# LilypadShield.net
KiCad netlist of a schematic drawn in EAGLE
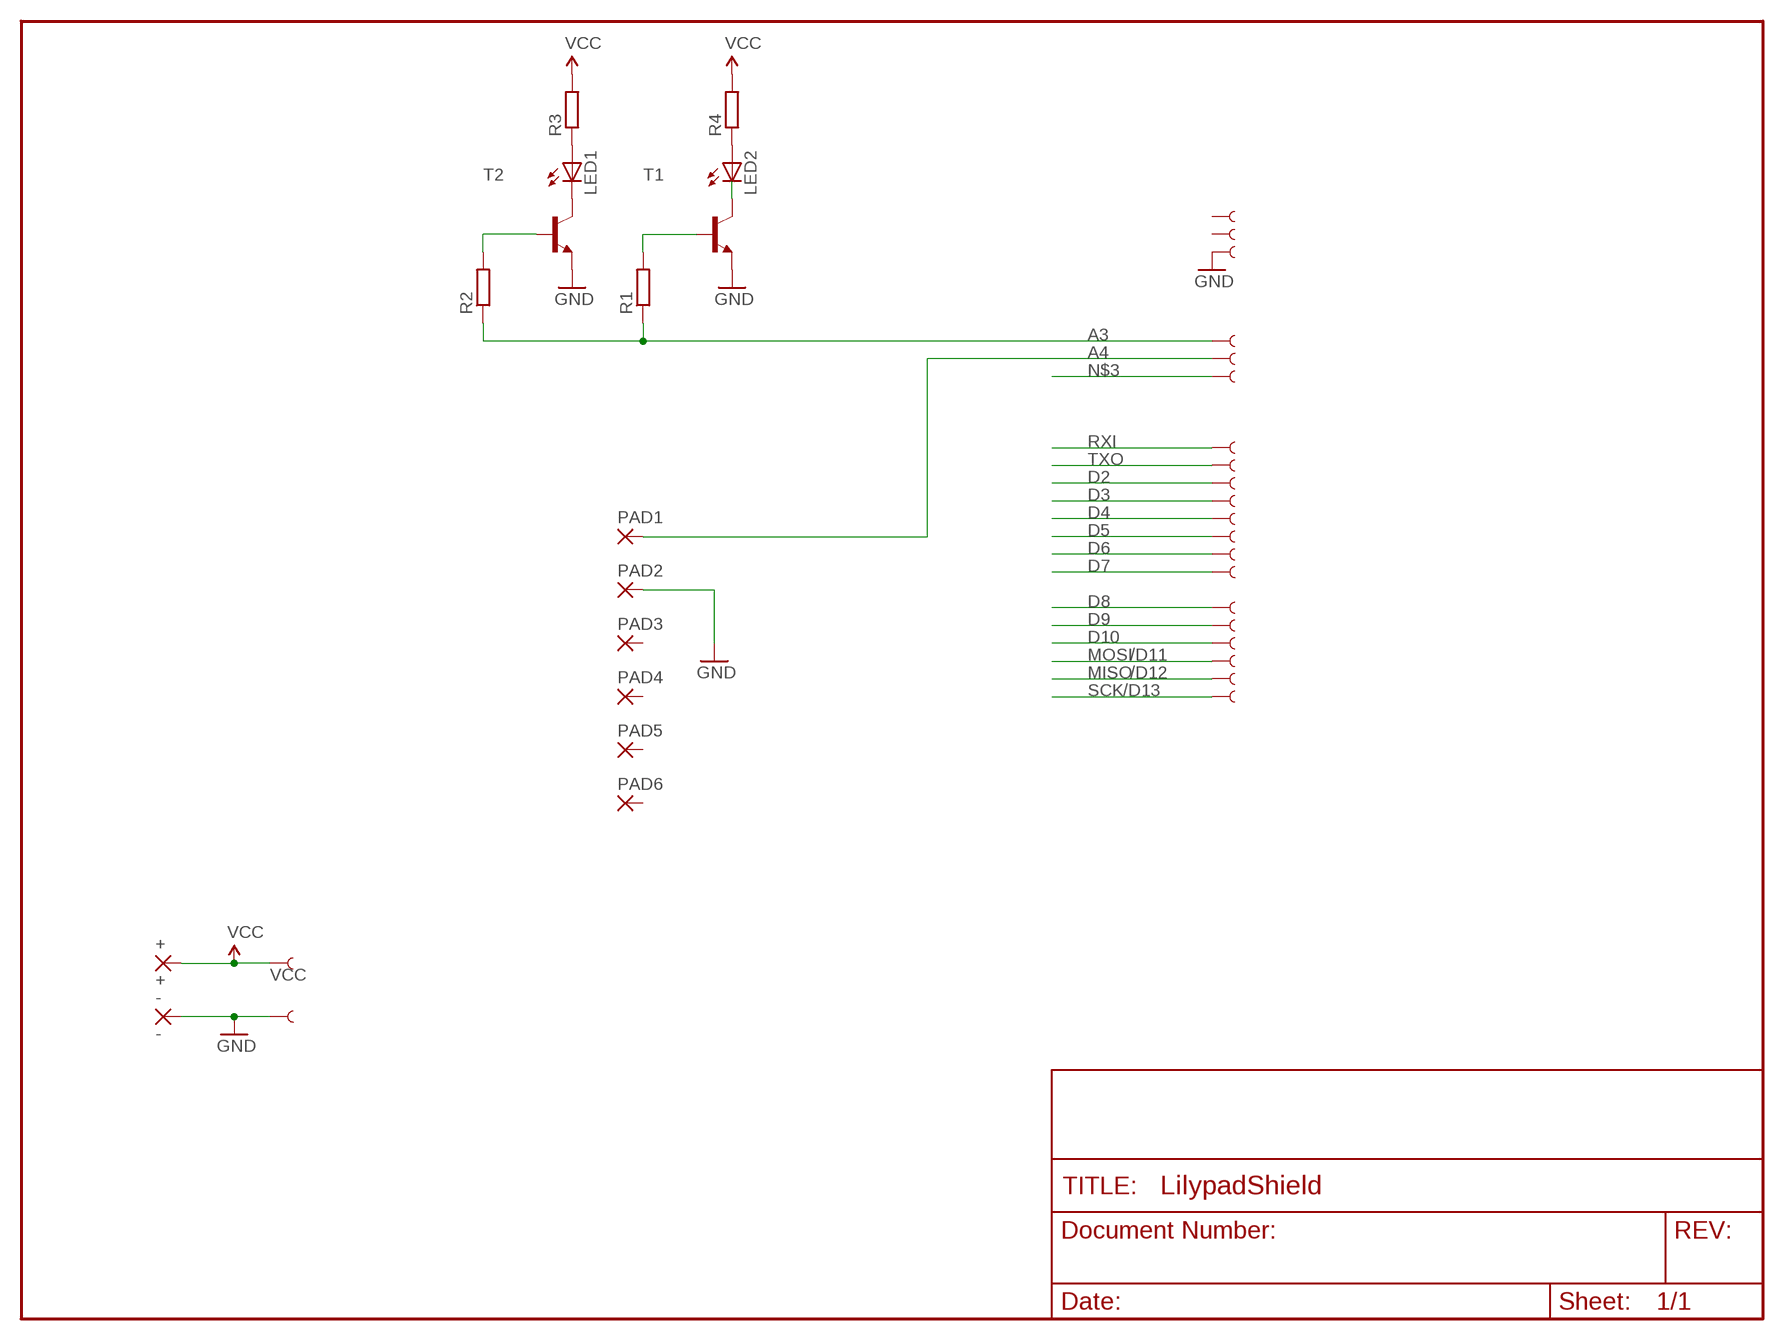
[diagram p0: schematic, sheet 1]

(export (version "E")
  (design (tool "Eeschema 10.0.6"))
  (components
    (comp (ref "+")
      (value "+")
      (footprint "eagle-import:1,6_0,8")
      (libsource (lib "eagle-import") (part "1,6/0,8"))
    )
    (comp (ref "-")
      (value "-")
      (footprint "eagle-import:1,6_0,8")
      (libsource (lib "eagle-import") (part "1,6/0,8"))
    )
    (comp (ref "GND")
      (value "SEWTAP1")
      (footprint "eagle-import:SEWTAP")
      (libsource (lib "eagle-import") (part "SEWTAP1"))
    )
    (comp (ref "LED1")
      (value "LED5MM")
      (footprint "eagle-import:LED5MM")
      (libsource (lib "eagle-import") (part "LED5MM"))
    )
    (comp (ref "LED2")
      (value "LED5MM")
      (footprint "eagle-import:LED5MM")
      (libsource (lib "eagle-import") (part "LED5MM"))
    )
    (comp (ref "PAD1")
      (value "1,6/0,8")
      (footprint "eagle-import:1,6_0,8")
      (libsource (lib "eagle-import") (part "1,6/0,8"))
    )
    (comp (ref "PAD2")
      (value "1,6/0,8")
      (footprint "eagle-import:1,6_0,8")
      (libsource (lib "eagle-import") (part "1,6/0,8"))
    )
    (comp (ref "PAD3")
      (value "1,6/0,8")
      (footprint "eagle-import:1,6_0,8")
      (libsource (lib "eagle-import") (part "1,6/0,8"))
    )
    (comp (ref "PAD4")
      (value "1,6/0,8")
      (footprint "eagle-import:1,6_0,8")
      (libsource (lib "eagle-import") (part "1,6/0,8"))
    )
    (comp (ref "PAD5")
      (value "1,6/0,8")
      (footprint "eagle-import:1,6_0,8")
      (libsource (lib "eagle-import") (part "1,6/0,8"))
    )
    (comp (ref "PAD6")
      (value "1,6/0,8")
      (footprint "eagle-import:1,6_0,8")
      (libsource (lib "eagle-import") (part "1,6/0,8"))
    )
    (comp (ref "R1")
      (value "R-EU_0204/5")
      (footprint "eagle-import:0204_5")
      (libsource (lib "eagle-import") (part "R-EU_0204/5"))
    )
    (comp (ref "R2")
      (value "R-EU_0204/5")
      (footprint "eagle-import:0204_5")
      (libsource (lib "eagle-import") (part "R-EU_0204/5"))
    )
    (comp (ref "R3")
      (value "R-EU_0204/5")
      (footprint "eagle-import:0204_5")
      (libsource (lib "eagle-import") (part "R-EU_0204/5"))
    )
    (comp (ref "R4")
      (value "R-EU_0204/5")
      (footprint "eagle-import:0204_5")
      (libsource (lib "eagle-import") (part "R-EU_0204/5"))
    )
    (comp (ref "T1")
      (value "2N3904")
      (footprint "eagle-import:TO92")
      (libsource (lib "eagle-import") (part "2N3904"))
    )
    (comp (ref "T2")
      (value "2N3904")
      (footprint "eagle-import:TO92")
      (libsource (lib "eagle-import") (part "2N3904"))
    )
    (comp (ref "U$4")
      (value "SEWTAP1")
      (footprint "eagle-import:SEWTAP")
      (libsource (lib "eagle-import") (part "SEWTAP1"))
    )
    (comp (ref "U$30")
      (value "SEWTAP1")
      (footprint "eagle-import:SEWTAP")
      (libsource (lib "eagle-import") (part "SEWTAP1"))
    )
    (comp (ref "U$31")
      (value "SEWTAP1")
      (footprint "eagle-import:SEWTAP")
      (libsource (lib "eagle-import") (part "SEWTAP1"))
    )
    (comp (ref "U$32")
      (value "SEWTAP1")
      (footprint "eagle-import:SEWTAP")
      (libsource (lib "eagle-import") (part "SEWTAP1"))
    )
    (comp (ref "U$33")
      (value "SEWTAP1")
      (footprint "eagle-import:SEWTAP")
      (libsource (lib "eagle-import") (part "SEWTAP1"))
    )
    (comp (ref "U$34")
      (value "SEWTAP1")
      (footprint "eagle-import:SEWTAP")
      (libsource (lib "eagle-import") (part "SEWTAP1"))
    )
    (comp (ref "U$35")
      (value "SEWTAP1")
      (footprint "eagle-import:SEWTAP")
      (libsource (lib "eagle-import") (part "SEWTAP1"))
    )
    (comp (ref "U$36")
      (value "SEWTAP1")
      (footprint "eagle-import:SEWTAP")
      (libsource (lib "eagle-import") (part "SEWTAP1"))
    )
    (comp (ref "U$37")
      (value "SEWTAP1")
      (footprint "eagle-import:SEWTAP")
      (libsource (lib "eagle-import") (part "SEWTAP1"))
    )
    (comp (ref "U$38")
      (value "SEWTAP1")
      (footprint "eagle-import:SEWTAP")
      (libsource (lib "eagle-import") (part "SEWTAP1"))
    )
    (comp (ref "U$39")
      (value "SEWTAP1")
      (footprint "eagle-import:SEWTAP")
      (libsource (lib "eagle-import") (part "SEWTAP1"))
    )
    (comp (ref "U$40")
      (value "SEWTAP1")
      (footprint "eagle-import:SEWTAP")
      (libsource (lib "eagle-import") (part "SEWTAP1"))
    )
    (comp (ref "U$41")
      (value "SEWTAP1")
      (footprint "eagle-import:SEWTAP")
      (libsource (lib "eagle-import") (part "SEWTAP1"))
    )
    (comp (ref "U$42")
      (value "SEWTAP1")
      (footprint "eagle-import:SEWTAP")
      (libsource (lib "eagle-import") (part "SEWTAP1"))
    )
    (comp (ref "U$43")
      (value "SEWTAP1")
      (footprint "eagle-import:SEWTAP")
      (libsource (lib "eagle-import") (part "SEWTAP1"))
    )
    (comp (ref "U$44")
      (value "SEWTAP1")
      (footprint "eagle-import:SEWTAP")
      (libsource (lib "eagle-import") (part "SEWTAP1"))
    )
    (comp (ref "U$45")
      (value "SEWTAP1")
      (footprint "eagle-import:SEWTAP")
      (libsource (lib "eagle-import") (part "SEWTAP1"))
    )
    (comp (ref "U$46")
      (value "SEWTAP1")
      (footprint "eagle-import:SEWTAP")
      (libsource (lib "eagle-import") (part "SEWTAP1"))
    )
    (comp (ref "U$47")
      (value "SEWTAP1")
      (footprint "eagle-import:SEWTAP")
      (libsource (lib "eagle-import") (part "SEWTAP1"))
    )
    (comp (ref "U$48")
      (value "SEWTAP1")
      (footprint "eagle-import:SEWTAP")
      (libsource (lib "eagle-import") (part "SEWTAP1"))
    )
    (comp (ref "U$51")
      (value "SEWTAP1")
      (footprint "eagle-import:SEWTAP")
      (libsource (lib "eagle-import") (part "SEWTAP1"))
    )
  )
  (nets
    (net (code "1") (name "/A3") (class "Default")
      (node (ref "R1") (pin "1") (pinfunction "1_1") (pintype "passive"))
      (node (ref "R2") (pin "1") (pinfunction "1_1") (pintype "passive"))
      (node (ref "U$32") (pin "1") (pinfunction "1_1") (pintype "bidirectional"))
    )
    (net (code "2") (name "/A4") (class "Default")
      (node (ref "PAD1") (pin "1") (pinfunction "P_1") (pintype "passive"))
      (node (ref "U$33") (pin "1") (pinfunction "1_1") (pintype "bidirectional"))
    )
    (net (code "3") (name "/D2") (class "Default")
      (node (ref "U$45") (pin "1") (pinfunction "1_1") (pintype "bidirectional"))
    )
    (net (code "4") (name "/D3") (class "Default")
      (node (ref "U$44") (pin "1") (pinfunction "1_1") (pintype "bidirectional"))
    )
    (net (code "5") (name "/D4") (class "Default")
      (node (ref "U$43") (pin "1") (pinfunction "1_1") (pintype "bidirectional"))
    )
    (net (code "6") (name "/D5") (class "Default")
      (node (ref "U$42") (pin "1") (pinfunction "1_1") (pintype "bidirectional"))
    )
    (net (code "7") (name "/D6") (class "Default")
      (node (ref "U$41") (pin "1") (pinfunction "1_1") (pintype "bidirectional"))
    )
    (net (code "8") (name "/D7") (class "Default")
      (node (ref "U$48") (pin "1") (pinfunction "1_1") (pintype "bidirectional"))
    )
    (net (code "9") (name "/D8") (class "Default")
      (node (ref "U$35") (pin "1") (pinfunction "1_1") (pintype "bidirectional"))
    )
    (net (code "10") (name "/D9") (class "Default")
      (node (ref "U$36") (pin "1") (pinfunction "1_1") (pintype "bidirectional"))
    )
    (net (code "11") (name "/D10") (class "Default")
      (node (ref "U$37") (pin "1") (pinfunction "1_1") (pintype "bidirectional"))
    )
    (net (code "12") (name "/MISO") (class "Default")
      (node (ref "U$39") (pin "1") (pinfunction "1_1") (pintype "bidirectional"))
    )
    (net (code "13") (name "/MOSI") (class "Default")
      (node (ref "U$38") (pin "1") (pinfunction "1_1") (pintype "bidirectional"))
    )
    (net (code "14") (name "/N$3") (class "Default")
      (node (ref "U$34") (pin "1") (pinfunction "1_1") (pintype "bidirectional"))
    )
    (net (code "15") (name "/RXI") (class "Default")
      (node (ref "U$47") (pin "1") (pinfunction "1_1") (pintype "bidirectional"))
    )
    (net (code "16") (name "/SCK") (class "Default")
      (node (ref "U$40") (pin "1") (pinfunction "1_1") (pintype "bidirectional"))
    )
    (net (code "17") (name "/TXO") (class "Default")
      (node (ref "U$46") (pin "1") (pinfunction "1_1") (pintype "bidirectional"))
    )
    (net (code "18") (name "GND") (class "Default")
      (node (ref "-") (pin "1") (pinfunction "P_1") (pintype "passive"))
      (node (ref "PAD2") (pin "1") (pinfunction "P_1") (pintype "passive"))
      (node (ref "T1") (pin "3") (pinfunction "E_3") (pintype "passive"))
      (node (ref "T2") (pin "3") (pinfunction "E_3") (pintype "passive"))
      (node (ref "U$30") (pin "1") (pinfunction "1_1") (pintype "bidirectional"))
      (node (ref "U$31") (pin "1") (pinfunction "1_1") (pintype "bidirectional"))
    )
    (net (code "19") (name "Net-(LED1-C)") (class "Default")
      (node (ref "LED1") (pin "K") (pinfunction "C_K") (pintype "passive"))
      (node (ref "T2") (pin "1") (pinfunction "C_1") (pintype "passive"))
    )
    (net (code "20") (name "Net-(LED1-PadA)") (class "Default")
      (node (ref "LED1") (pin "A") (pinfunction "A_A") (pintype "passive"))
      (node (ref "R3") (pin "1") (pinfunction "1_1") (pintype "passive"))
    )
    (net (code "21") (name "Net-(LED2-C)") (class "Default")
      (node (ref "LED2") (pin "K") (pinfunction "C_K") (pintype "passive"))
      (node (ref "T1") (pin "1") (pinfunction "C_1") (pintype "passive"))
    )
    (net (code "22") (name "Net-(LED2-PadA)") (class "Default")
      (node (ref "LED2") (pin "A") (pinfunction "A_A") (pintype "passive"))
      (node (ref "R4") (pin "1") (pinfunction "1_1") (pintype "passive"))
    )
    (net (code "23") (name "Net-(T1-B)") (class "Default")
      (node (ref "R1") (pin "2") (pinfunction "2_2") (pintype "passive"))
      (node (ref "T1") (pin "2") (pinfunction "B_2") (pintype "passive"))
    )
    (net (code "24") (name "Net-(T2-B)") (class "Default")
      (node (ref "R2") (pin "2") (pinfunction "2_2") (pintype "passive"))
      (node (ref "T2") (pin "2") (pinfunction "B_2") (pintype "passive"))
    )
    (net (code "25") (name "VCC") (class "Default")
      (node (ref "+") (pin "1") (pinfunction "P_1") (pintype "passive"))
      (node (ref "R3") (pin "2") (pinfunction "2_2") (pintype "passive"))
      (node (ref "R4") (pin "2") (pinfunction "2_2") (pintype "passive"))
      (node (ref "U$4") (pin "1") (pinfunction "1_1") (pintype "bidirectional"))
    )
    (net (code "26") (name "unconnected-(GND-Pad1)") (class "Default")
      (node (ref "GND") (pin "1") (pinfunction "1_1") (pintype "bidirectional"))
    )
    (net (code "27") (name "unconnected-(PAD3-P-Pad1)") (class "Default")
      (node (ref "PAD3") (pin "1") (pinfunction "P_1") (pintype "passive"))
    )
    (net (code "28") (name "unconnected-(PAD4-P-Pad1)") (class "Default")
      (node (ref "PAD4") (pin "1") (pinfunction "P_1") (pintype "passive"))
    )
    (net (code "29") (name "unconnected-(PAD5-P-Pad1)") (class "Default")
      (node (ref "PAD5") (pin "1") (pinfunction "P_1") (pintype "passive"))
    )
    (net (code "30") (name "unconnected-(PAD6-P-Pad1)") (class "Default")
      (node (ref "PAD6") (pin "1") (pinfunction "P_1") (pintype "passive"))
    )
    (net (code "31") (name "unconnected-(U$51-Pad1)") (class "Default")
      (node (ref "U$51") (pin "1") (pinfunction "1_1") (pintype "bidirectional"))
    )
  )
)
